# 5volt_v0_1.net
KiCad netlist of a schematic drawn in EAGLE
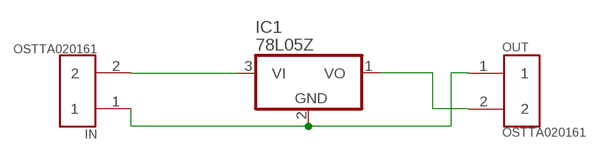
[diagram p0: schematic, sheet 1]

(export (version "E")
  (design (tool "Eeschema 10.0.6"))
  (components
    (comp (ref "IC1")
      (value "78L05Z")
      (footprint "eagle-import:TO92")
      (libsource (lib "eagle-import") (part "78ZL05"))
    )
    (comp (ref "IN")
      (value "OSTTA020161")
      (footprint "eagle-import:OST_OSTTA020161")
      (fields (field (name "MF") "On Shore"))
      (libsource (lib "eagle-import") (part "OSTTA020161"))
    )
    (comp (ref "OUT")
      (value "OSTTA020161")
      (footprint "eagle-import:OST_OSTTA020161")
      (fields (field (name "MF") "On Shore"))
      (libsource (lib "eagle-import") (part "OSTTA020161"))
    )
  )
  (nets
    (net (code "1") (name "Net-(IC1-GND)") (class "Default")
      (node (ref "IC1") (pin "2") (pinfunction "GND_2") (pintype "passive"))
      (node (ref "IN") (pin "1") (pinfunction "1_1") (pintype "passive"))
      (node (ref "OUT") (pin "1") (pinfunction "1_1") (pintype "passive"))
    )
    (net (code "2") (name "Net-(IC1-VI)") (class "Default")
      (node (ref "IC1") (pin "3") (pinfunction "VI_3") (pintype "input"))
      (node (ref "IN") (pin "2") (pinfunction "2_2") (pintype "passive"))
    )
    (net (code "3") (name "Net-(IC1-VO)") (class "Default")
      (node (ref "IC1") (pin "1") (pinfunction "VO_1") (pintype "passive"))
      (node (ref "OUT") (pin "2") (pinfunction "2_2") (pintype "passive"))
    )
  )
)
